# BUF_1U_6HP_fpb.net
KiCad netlist of a schematic drawn in EAGLE
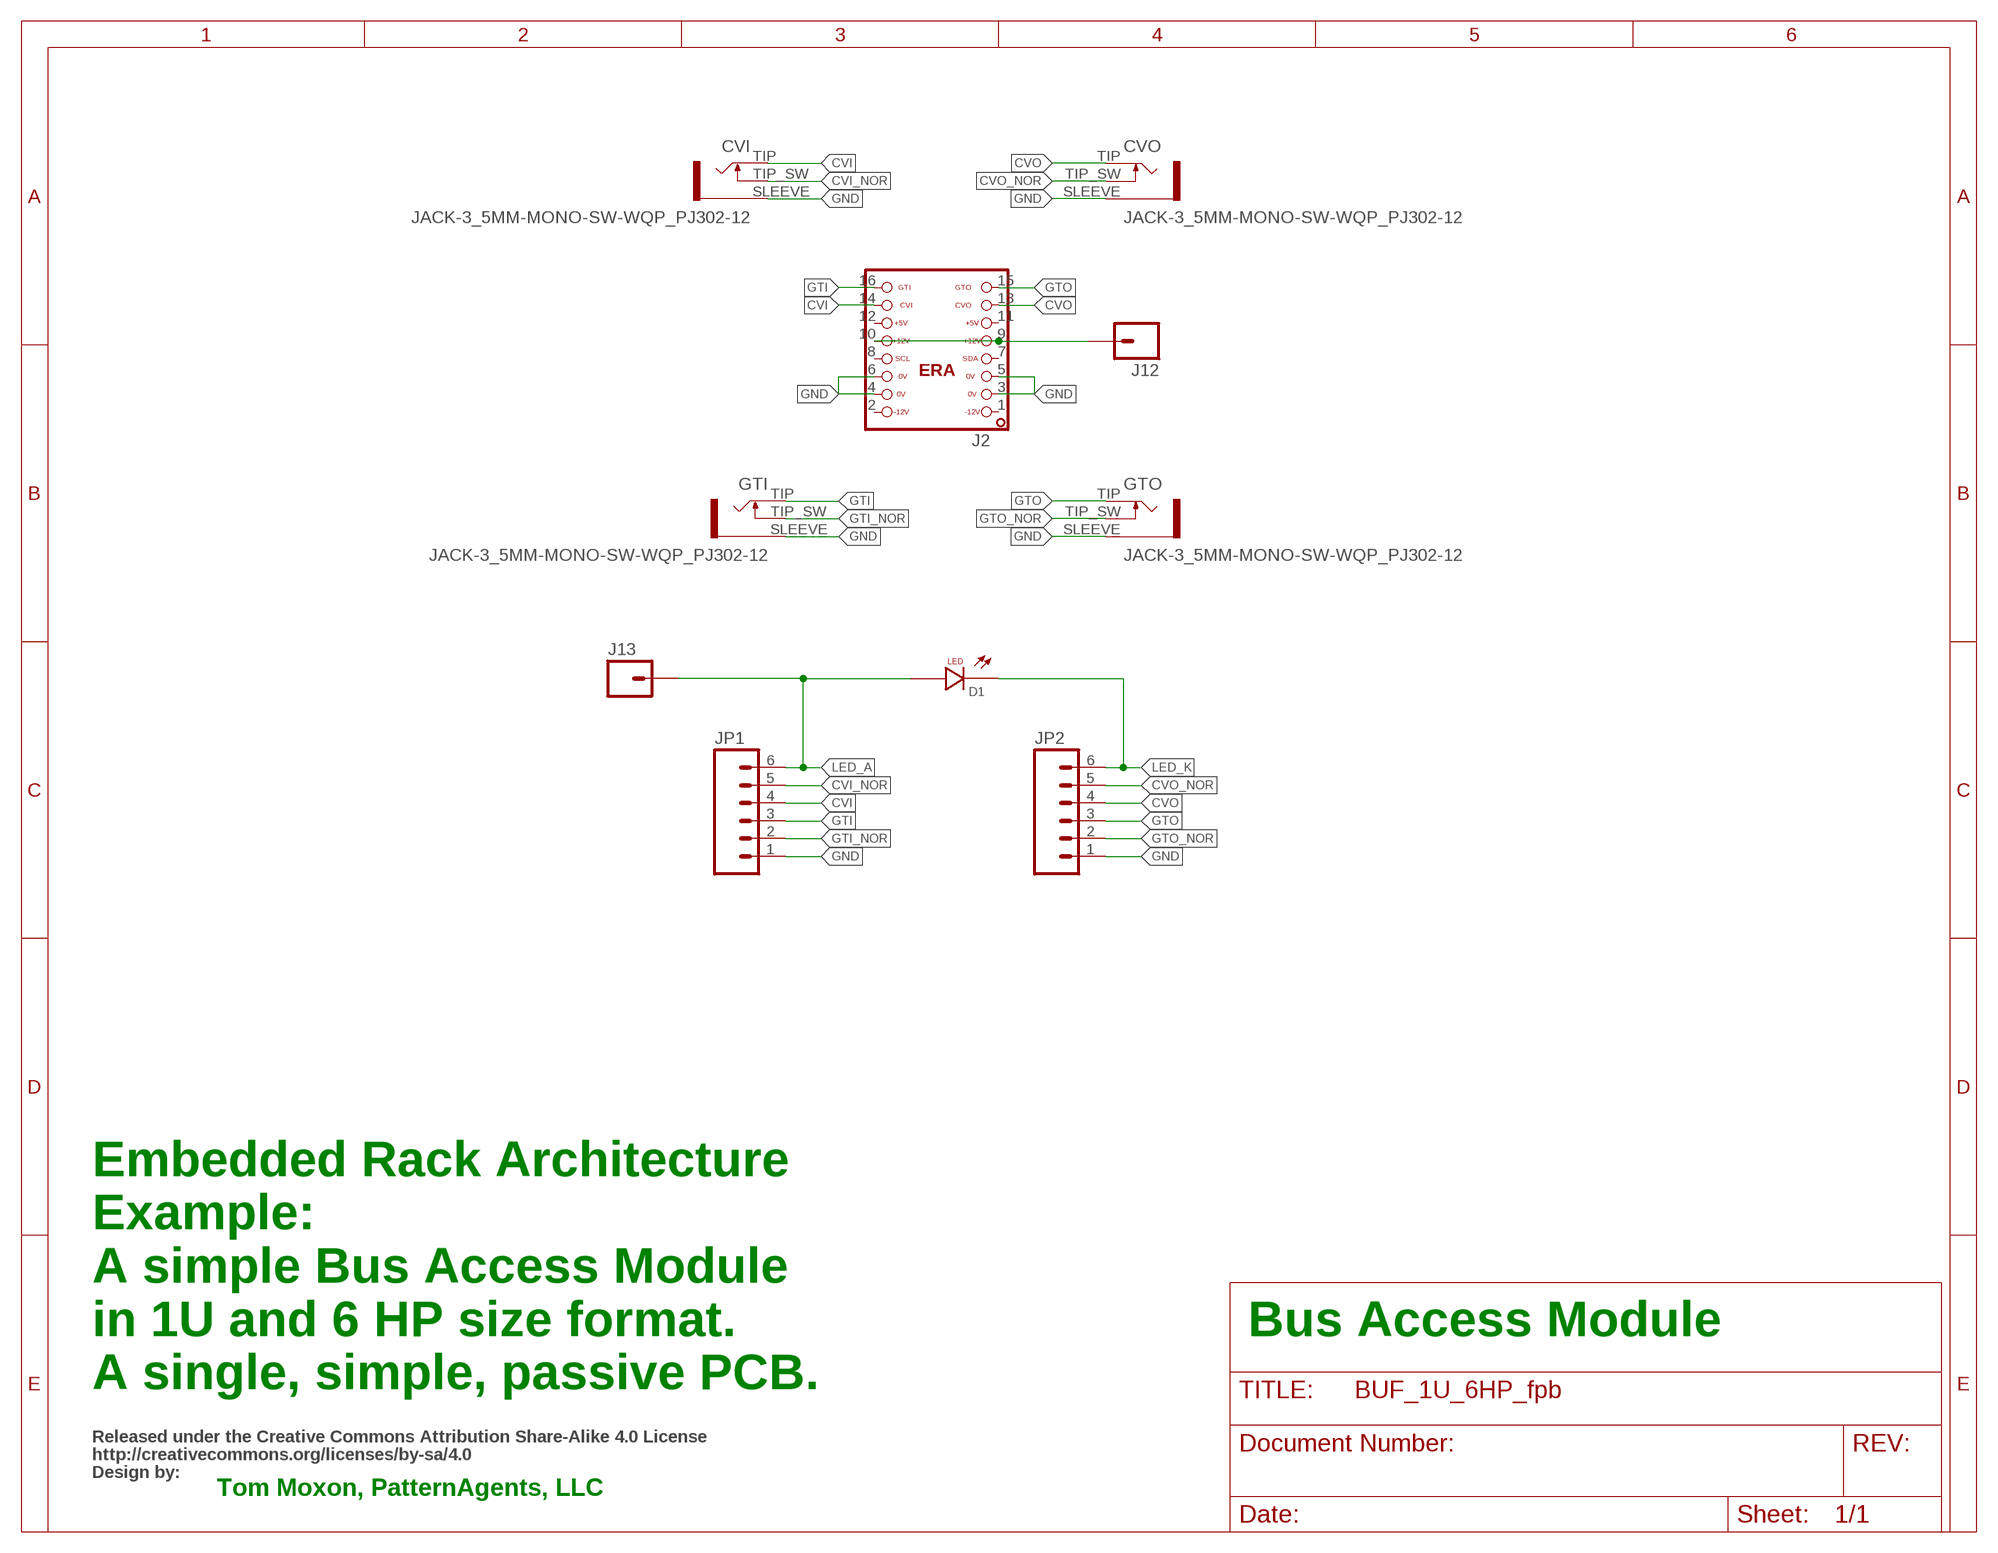
[diagram p0: schematic, sheet 1]

(export (version "E")
  (design (tool "Eeschema 10.0.6"))
  (components
    (comp (ref "CVI")
      (value "JACK-3_5MM-MONO-SW-WQP_PJ302-12")
      (footprint "eagle-import:WQP_PJ301M-12")
      (libsource (lib "eagle-import") (part "JACK-3_5MM-MONO-SW-WQP_PJ302-12"))
    )
    (comp (ref "CVO")
      (value "JACK-3_5MM-MONO-SW-WQP_PJ302-12")
      (footprint "eagle-import:WQP_PJ301M-12")
      (libsource (lib "eagle-import") (part "JACK-3_5MM-MONO-SW-WQP_PJ302-12"))
    )
    (comp (ref "D1")
      (value "LED")
      (footprint "eagle-import:LED3MM")
      (libsource (lib "eagle-import") (part "LED"))
    )
    (comp (ref "GTI")
      (value "JACK-3_5MM-MONO-SW-WQP_PJ302-12")
      (footprint "eagle-import:WQP_PJ301M-12")
      (libsource (lib "eagle-import") (part "JACK-3_5MM-MONO-SW-WQP_PJ302-12"))
    )
    (comp (ref "GTO")
      (value "JACK-3_5MM-MONO-SW-WQP_PJ302-12")
      (footprint "eagle-import:WQP_PJ301M-12")
      (libsource (lib "eagle-import") (part "JACK-3_5MM-MONO-SW-WQP_PJ302-12"))
    )
    (comp (ref "J2")
      (value "ERA-NOSILK")
      (footprint "eagle-import:ERA-NOSILK")
      (libsource (lib "eagle-import") (part "ERA-NOSILK"))
    )
    (comp (ref "J12")
      (value "M01PTH")
      (footprint "eagle-import:1X01")
      (libsource (lib "eagle-import") (part "M01PTH"))
    )
    (comp (ref "J13")
      (value "M01PTH")
      (footprint "eagle-import:1X01")
      (libsource (lib "eagle-import") (part "M01PTH"))
    )
    (comp (ref "JP1")
      (value "M06SIP")
      (footprint "eagle-import:1X06")
      (libsource (lib "eagle-import") (part "M06SIP"))
    )
    (comp (ref "JP2")
      (value "M06SIP")
      (footprint "eagle-import:1X06")
      (libsource (lib "eagle-import") (part "M06SIP"))
    )
    (comp (ref "TOMMOXON")
      (value "BY_CC_SA_TEXTNULL")
      (footprint "eagle-import:NULL_SYM")
      (libsource (lib "eagle-import") (part "BY_CC_SA_TEXTNULL"))
    )
  )
  (nets
    (net (code "1") (name "CVI") (class "Default")
      (node (ref "CVI") (pin "TIP") (pinfunction "TIP_TIP") (pintype "passive"))
      (node (ref "J2") (pin "14") (pinfunction "14_14") (pintype "passive"))
      (node (ref "JP1") (pin "4") (pinfunction "4_4") (pintype "passive"))
    )
    (net (code "2") (name "CVI_NOR") (class "Default")
      (node (ref "CVI") (pin "TIP_SW") (pinfunction "TIP_SW_TIP_SW") (pintype "passive"))
      (node (ref "JP1") (pin "5") (pinfunction "5_5") (pintype "passive"))
    )
    (net (code "3") (name "CVO") (class "Default")
      (node (ref "CVO") (pin "TIP") (pinfunction "TIP_TIP") (pintype "passive"))
      (node (ref "J2") (pin "13") (pinfunction "13_13") (pintype "passive"))
      (node (ref "JP2") (pin "4") (pinfunction "4_4") (pintype "passive"))
    )
    (net (code "4") (name "CVO_NOR") (class "Default")
      (node (ref "CVO") (pin "TIP_SW") (pinfunction "TIP_SW_TIP_SW") (pintype "passive"))
      (node (ref "JP2") (pin "5") (pinfunction "5_5") (pintype "passive"))
    )
    (net (code "5") (name "GND") (class "Default")
      (node (ref "CVI") (pin "SLEEVE") (pinfunction "SLEEVE_SLEEVE") (pintype "passive"))
      (node (ref "CVO") (pin "SLEEVE") (pinfunction "SLEEVE_SLEEVE") (pintype "passive"))
      (node (ref "GTI") (pin "SLEEVE") (pinfunction "SLEEVE_SLEEVE") (pintype "passive"))
      (node (ref "GTO") (pin "SLEEVE") (pinfunction "SLEEVE_SLEEVE") (pintype "passive"))
      (node (ref "J2") (pin "3") (pinfunction "3_3") (pintype "passive"))
      (node (ref "J2") (pin "4") (pinfunction "4_4") (pintype "passive"))
      (node (ref "J2") (pin "5") (pinfunction "5_5") (pintype "passive"))
      (node (ref "J2") (pin "6") (pinfunction "6_6") (pintype "passive"))
      (node (ref "JP1") (pin "1") (pinfunction "1_1") (pintype "passive"))
      (node (ref "JP2") (pin "1") (pinfunction "1_1") (pintype "passive"))
    )
    (net (code "6") (name "GTI") (class "Default")
      (node (ref "GTI") (pin "TIP") (pinfunction "TIP_TIP") (pintype "passive"))
      (node (ref "J2") (pin "16") (pinfunction "16_16") (pintype "passive"))
      (node (ref "JP1") (pin "3") (pinfunction "3_3") (pintype "passive"))
    )
    (net (code "7") (name "GTI_NOR") (class "Default")
      (node (ref "GTI") (pin "TIP_SW") (pinfunction "TIP_SW_TIP_SW") (pintype "passive"))
      (node (ref "JP1") (pin "2") (pinfunction "2_2") (pintype "passive"))
    )
    (net (code "8") (name "GTO") (class "Default")
      (node (ref "GTO") (pin "TIP") (pinfunction "TIP_TIP") (pintype "passive"))
      (node (ref "J2") (pin "15") (pinfunction "15_15") (pintype "passive"))
      (node (ref "JP2") (pin "3") (pinfunction "3_3") (pintype "passive"))
    )
    (net (code "9") (name "GTO_NOR") (class "Default")
      (node (ref "GTO") (pin "TIP_SW") (pinfunction "TIP_SW_TIP_SW") (pintype "passive"))
      (node (ref "JP2") (pin "2") (pinfunction "2_2") (pintype "passive"))
    )
    (net (code "10") (name "LED_A") (class "Default")
      (node (ref "D1") (pin "A") (pinfunction "ANODE_A") (pintype "bidirectional"))
      (node (ref "J13") (pin "1") (pinfunction "1_1") (pintype "passive"))
      (node (ref "JP1") (pin "6") (pinfunction "6_6") (pintype "passive"))
    )
    (net (code "11") (name "LED_K") (class "Default")
      (node (ref "D1") (pin "K") (pinfunction "CATHODE_K") (pintype "bidirectional"))
      (node (ref "JP2") (pin "6") (pinfunction "6_6") (pintype "passive"))
    )
    (net (code "12") (name "Net-(J12-Pad1)") (class "Default")
      (node (ref "J12") (pin "1") (pinfunction "1_1") (pintype "passive"))
      (node (ref "J2") (pin "10") (pinfunction "10_10") (pintype "passive"))
      (node (ref "J2") (pin "9") (pinfunction "9_9") (pintype "passive"))
    )
    (net (code "13") (name "unconnected-(J2-Pad1)") (class "Default")
      (node (ref "J2") (pin "1") (pinfunction "1_1") (pintype "passive"))
    )
    (net (code "14") (name "unconnected-(J2-Pad2)") (class "Default")
      (node (ref "J2") (pin "2") (pinfunction "2_2") (pintype "passive"))
    )
    (net (code "15") (name "unconnected-(J2-Pad7)") (class "Default")
      (node (ref "J2") (pin "7") (pinfunction "7_7") (pintype "passive"))
    )
    (net (code "16") (name "unconnected-(J2-Pad8)") (class "Default")
      (node (ref "J2") (pin "8") (pinfunction "8_8") (pintype "passive"))
    )
    (net (code "17") (name "unconnected-(J2-Pad11)") (class "Default")
      (node (ref "J2") (pin "11") (pinfunction "11_11") (pintype "passive"))
    )
    (net (code "18") (name "unconnected-(J2-Pad12)") (class "Default")
      (node (ref "J2") (pin "12") (pinfunction "12_12") (pintype "passive"))
    )
  )
)
